# sch_AGV_MCU.net
KiCad netlist of a schematic drawn in Altium Designer
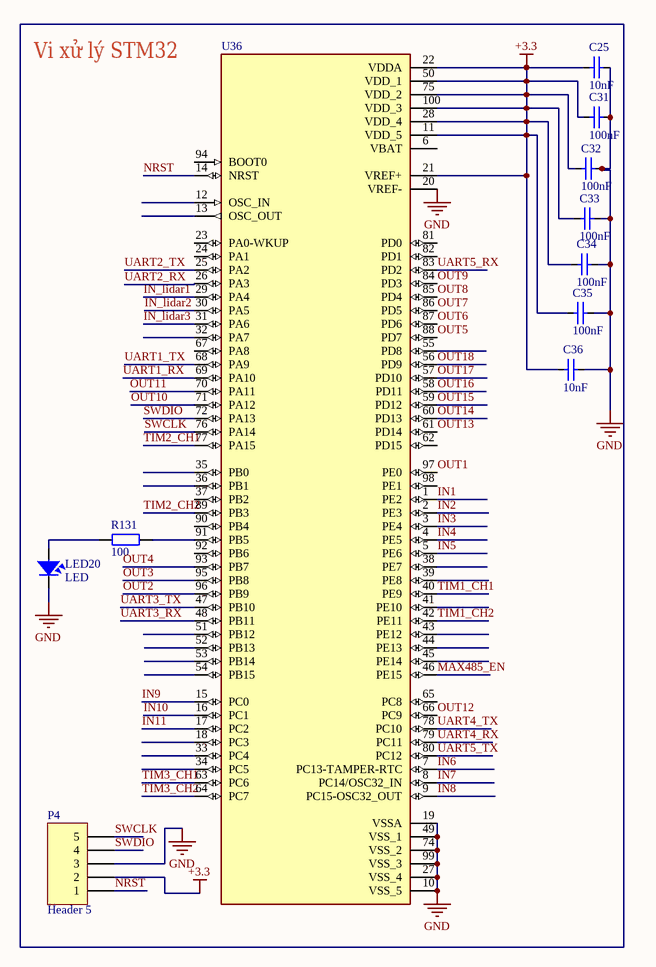
[diagram p0: sch_AGV_MCU.SchDoc]

(export (version "E")
  (design (tool "Eeschema 10.0.6"))
  (components
    (comp (ref "C25")
      (value "10nF")
      (footprint "CAP_0805")
      (description "Capacitor")
      (fields (field (name "PUBLISHER") "Altium Limited"))
      (libsource (lib "schelib_AGVcontrol") (part "CapSMD"))
    )
    (comp (ref "C31")
      (value "100nF")
      (footprint "CAP_0805")
      (description "Capacitor")
      (fields (field (name "PUBLISHER") "Altium Limited"))
      (libsource (lib "schelib_AGVcontrol") (part "CapSMD"))
    )
    (comp (ref "C32")
      (value "100nF")
      (footprint "CAP_0805")
      (description "Capacitor")
      (fields (field (name "PUBLISHER") "Altium Limited"))
      (libsource (lib "schelib_AGVcontrol") (part "CapSMD"))
    )
    (comp (ref "C33")
      (value "100nF")
      (footprint "CAP_0805")
      (description "Capacitor")
      (fields (field (name "PUBLISHER") "Altium Limited"))
      (libsource (lib "schelib_AGVcontrol") (part "CapSMD"))
    )
    (comp (ref "C34")
      (value "100nF")
      (footprint "CAP_0805")
      (description "Capacitor")
      (fields (field (name "PUBLISHER") "Altium Limited"))
      (libsource (lib "schelib_AGVcontrol") (part "CapSMD"))
    )
    (comp (ref "C35")
      (value "100nF")
      (footprint "CAP_0805")
      (description "Capacitor")
      (fields (field (name "PUBLISHER") "Altium Limited"))
      (libsource (lib "schelib_AGVcontrol") (part "CapSMD"))
    )
    (comp (ref "C36")
      (value "10nF")
      (footprint "CAP_0805")
      (description "Capacitor")
      (fields (field (name "PUBLISHER") "Altium Limited"))
      (libsource (lib "schelib_AGVcontrol") (part "CapSMD"))
    )
    (comp (ref "LED20")
      (value "LED")
      (footprint "LED_BLUE_SMD_0805")
      (description "LED Single colour Green and Red")
      (libsource (lib "schelib_AGVcontrol") (part "LED"))
    )
    (comp (ref "P4")
      (value "Header 5")
      (footprint "HDR5")
      (description "Header, 5-Pin")
      (fields (field (name "PUBLISHER") "Altium Limited"))
      (libsource (lib "schelib_AGVcontrol") (part "Header 5"))
    )
    (comp (ref "R131")
      (value "100")
      (footprint "RES_SMD_0805")
      (description "Resistor")
      (fields
        (field (name "MANUFACTURER") "Generic Components")
        (field (name "PUBLISHER") "Altium Hobart Technology Centre")
      )
      (libsource (lib "schelib_AGVcontrol") (part "Res"))
    )
    (comp (ref "U36")
      (value "~")
      (footprint "QFP50P1600X1600X160-100N")
      (description "ARMÂ® CortexÂ®-M3 STM32F1 Microcontroller IC 32-Bit 72MHz 512KB (512K x 8) FLASH 100-LQFP (14x14)")
      (fields (field (name "MF") "STMicroelectronics") (field (name "MP") "STM32F103VET6"))
      (libsource (lib "schelib_AGVcontrol") (part "STM32F103VET6"))
    )
  )
  (nets
    (net (code "1") (name "+3.3") (class "Default")
      (node (ref "C25") (pin "1") (pinfunction "1_1") (pintype "passive"))
      (node (ref "C31") (pin "1") (pinfunction "1_1") (pintype "passive"))
      (node (ref "C32") (pin "1") (pinfunction "1_1") (pintype "passive"))
      (node (ref "C33") (pin "1") (pinfunction "1_1") (pintype "passive"))
      (node (ref "C34") (pin "1") (pinfunction "1_1") (pintype "passive"))
      (node (ref "C35") (pin "1") (pinfunction "1_1") (pintype "passive"))
      (node (ref "C36") (pin "1") (pinfunction "1_1") (pintype "passive"))
      (node (ref "P4") (pin "2") (pinfunction "2_2") (pintype "passive"))
      (node (ref "U36") (pin "100") (pinfunction "VDD_3_100") (pintype "power_in"))
      (node (ref "U36") (pin "11") (pinfunction "VDD_5_11") (pintype "power_in"))
      (node (ref "U36") (pin "21") (pinfunction "VREF+_21") (pintype "power_in"))
      (node (ref "U36") (pin "22") (pinfunction "VDDA_22") (pintype "power_in"))
      (node (ref "U36") (pin "28") (pinfunction "VDD_4_28") (pintype "power_in"))
      (node (ref "U36") (pin "50") (pinfunction "VDD_1_50") (pintype "power_in"))
      (node (ref "U36") (pin "75") (pinfunction "VDD_2_75") (pintype "power_in"))
    )
    (net (code "2") (name "/IN1") (class "Default")
      (node (ref "U36") (pin "1") (pinfunction "PE2_1") (pintype "bidirectional"))
    )
    (net (code "3") (name "/IN2") (class "Default")
      (node (ref "U36") (pin "2") (pinfunction "PE3_2") (pintype "bidirectional"))
    )
    (net (code "4") (name "/IN3") (class "Default")
      (node (ref "U36") (pin "3") (pinfunction "PE4_3") (pintype "bidirectional"))
    )
    (net (code "5") (name "/IN4") (class "Default")
      (node (ref "U36") (pin "4") (pinfunction "PE5_4") (pintype "bidirectional"))
    )
    (net (code "6") (name "/IN5") (class "Default")
      (node (ref "U36") (pin "5") (pinfunction "PE6_5") (pintype "bidirectional"))
    )
    (net (code "7") (name "/IN6") (class "Default")
      (node (ref "U36") (pin "7") (pinfunction "PC13-TAMPER-RTC_7") (pintype "bidirectional"))
    )
    (net (code "8") (name "/IN7") (class "Default")
      (node (ref "U36") (pin "8") (pinfunction "PC14/OSC32_IN_8") (pintype "bidirectional"))
    )
    (net (code "9") (name "/IN8") (class "Default")
      (node (ref "U36") (pin "9") (pinfunction "PC15-OSC32_OUT_9") (pintype "bidirectional"))
    )
    (net (code "10") (name "/IN9") (class "Default")
      (node (ref "U36") (pin "15") (pinfunction "PC0_15") (pintype "bidirectional"))
    )
    (net (code "11") (name "/IN10") (class "Default")
      (node (ref "U36") (pin "16") (pinfunction "PC1_16") (pintype "bidirectional"))
    )
    (net (code "12") (name "/IN11") (class "Default")
      (node (ref "U36") (pin "17") (pinfunction "PC2_17") (pintype "bidirectional"))
    )
    (net (code "13") (name "/IN_lidar1") (class "Default")
      (node (ref "U36") (pin "29") (pinfunction "PA4_29") (pintype "bidirectional"))
    )
    (net (code "14") (name "/IN_lidar2") (class "Default")
      (node (ref "U36") (pin "30") (pinfunction "PA5_30") (pintype "bidirectional"))
    )
    (net (code "15") (name "/IN_lidar3") (class "Default")
      (node (ref "U36") (pin "31") (pinfunction "PA6_31") (pintype "bidirectional"))
    )
    (net (code "16") (name "/MAX485_EN") (class "Default")
      (node (ref "U36") (pin "46") (pinfunction "PE15_46") (pintype "bidirectional"))
    )
    (net (code "17") (name "/NRST") (class "Default")
      (node (ref "P4") (pin "1") (pinfunction "1_1") (pintype "passive"))
      (node (ref "U36") (pin "14") (pinfunction "NRST_14") (pintype "bidirectional"))
    )
    (net (code "18") (name "/OUT1") (class "Default")
      (node (ref "U36") (pin "97") (pinfunction "PE0_97") (pintype "bidirectional"))
    )
    (net (code "19") (name "/OUT2") (class "Default")
      (node (ref "U36") (pin "96") (pinfunction "PB9_96") (pintype "bidirectional"))
    )
    (net (code "20") (name "/OUT3") (class "Default")
      (node (ref "U36") (pin "95") (pinfunction "PB8_95") (pintype "bidirectional"))
    )
    (net (code "21") (name "/OUT4") (class "Default")
      (node (ref "U36") (pin "93") (pinfunction "PB7_93") (pintype "bidirectional"))
    )
    (net (code "22") (name "/OUT5") (class "Default")
      (node (ref "U36") (pin "88") (pinfunction "PD7_88") (pintype "bidirectional"))
    )
    (net (code "23") (name "/OUT6") (class "Default")
      (node (ref "U36") (pin "87") (pinfunction "PD6_87") (pintype "bidirectional"))
    )
    (net (code "24") (name "/OUT7") (class "Default")
      (node (ref "U36") (pin "86") (pinfunction "PD5_86") (pintype "bidirectional"))
    )
    (net (code "25") (name "/OUT8") (class "Default")
      (node (ref "U36") (pin "85") (pinfunction "PD4_85") (pintype "bidirectional"))
    )
    (net (code "26") (name "/OUT9") (class "Default")
      (node (ref "U36") (pin "84") (pinfunction "PD3_84") (pintype "bidirectional"))
    )
    (net (code "27") (name "/OUT10") (class "Default")
      (node (ref "U36") (pin "71") (pinfunction "PA12_71") (pintype "bidirectional"))
    )
    (net (code "28") (name "/OUT11") (class "Default")
      (node (ref "U36") (pin "70") (pinfunction "PA11_70") (pintype "bidirectional"))
    )
    (net (code "29") (name "/OUT12") (class "Default")
      (node (ref "U36") (pin "66") (pinfunction "PC9_66") (pintype "bidirectional"))
    )
    (net (code "30") (name "/OUT13") (class "Default")
      (node (ref "U36") (pin "61") (pinfunction "PD14_61") (pintype "bidirectional"))
    )
    (net (code "31") (name "/OUT14") (class "Default")
      (node (ref "U36") (pin "60") (pinfunction "PD13_60") (pintype "bidirectional"))
    )
    (net (code "32") (name "/OUT15") (class "Default")
      (node (ref "U36") (pin "59") (pinfunction "PD12_59") (pintype "bidirectional"))
    )
    (net (code "33") (name "/OUT16") (class "Default")
      (node (ref "U36") (pin "58") (pinfunction "PD11_58") (pintype "bidirectional"))
    )
    (net (code "34") (name "/OUT17") (class "Default")
      (node (ref "U36") (pin "57") (pinfunction "PD10_57") (pintype "bidirectional"))
    )
    (net (code "35") (name "/OUT18") (class "Default")
      (node (ref "U36") (pin "56") (pinfunction "PD9_56") (pintype "bidirectional"))
    )
    (net (code "36") (name "/SWCLK") (class "Default")
      (node (ref "P4") (pin "5") (pinfunction "5_5") (pintype "passive"))
      (node (ref "U36") (pin "76") (pinfunction "PA14_76") (pintype "bidirectional"))
    )
    (net (code "37") (name "/SWDIO") (class "Default")
      (node (ref "P4") (pin "4") (pinfunction "4_4") (pintype "passive"))
      (node (ref "U36") (pin "72") (pinfunction "PA13_72") (pintype "bidirectional"))
    )
    (net (code "38") (name "/TIM1_CH1") (class "Default")
      (node (ref "U36") (pin "40") (pinfunction "PE9_40") (pintype "bidirectional"))
    )
    (net (code "39") (name "/TIM1_CH2") (class "Default")
      (node (ref "U36") (pin "42") (pinfunction "PE11_42") (pintype "bidirectional"))
    )
    (net (code "40") (name "/TIM2_CH1") (class "Default")
      (node (ref "U36") (pin "77") (pinfunction "PA15_77") (pintype "bidirectional"))
    )
    (net (code "41") (name "/TIM2_CH2") (class "Default")
      (node (ref "U36") (pin "89") (pinfunction "PB3_89") (pintype "bidirectional"))
    )
    (net (code "42") (name "/TIM3_CH1") (class "Default")
      (node (ref "U36") (pin "63") (pinfunction "PC6_63") (pintype "bidirectional"))
    )
    (net (code "43") (name "/TIM3_CH2") (class "Default")
      (node (ref "U36") (pin "64") (pinfunction "PC7_64") (pintype "bidirectional"))
    )
    (net (code "44") (name "/UART1_RX") (class "Default")
      (node (ref "U36") (pin "69") (pinfunction "PA10_69") (pintype "bidirectional"))
    )
    (net (code "45") (name "/UART1_TX") (class "Default")
      (node (ref "U36") (pin "68") (pinfunction "PA9_68") (pintype "bidirectional"))
    )
    (net (code "46") (name "/UART2_RX") (class "Default")
      (node (ref "U36") (pin "26") (pinfunction "PA3_26") (pintype "bidirectional"))
    )
    (net (code "47") (name "/UART2_TX") (class "Default")
      (node (ref "U36") (pin "25") (pinfunction "PA2_25") (pintype "bidirectional"))
    )
    (net (code "48") (name "/UART3_RX") (class "Default")
      (node (ref "U36") (pin "48") (pinfunction "PB11_48") (pintype "bidirectional"))
    )
    (net (code "49") (name "/UART3_TX") (class "Default")
      (node (ref "U36") (pin "47") (pinfunction "PB10_47") (pintype "bidirectional"))
    )
    (net (code "50") (name "/UART4_RX") (class "Default")
      (node (ref "U36") (pin "79") (pinfunction "PC11_79") (pintype "bidirectional"))
    )
    (net (code "51") (name "/UART4_TX") (class "Default")
      (node (ref "U36") (pin "78") (pinfunction "PC10_78") (pintype "bidirectional"))
    )
    (net (code "52") (name "/UART5_RX") (class "Default")
      (node (ref "U36") (pin "83") (pinfunction "PD2_83") (pintype "bidirectional"))
    )
    (net (code "53") (name "/UART5_TX") (class "Default")
      (node (ref "U36") (pin "80") (pinfunction "PC12_80") (pintype "bidirectional"))
    )
    (net (code "54") (name "GND") (class "Default")
      (node (ref "C25") (pin "2") (pinfunction "2_2") (pintype "passive"))
      (node (ref "C31") (pin "2") (pinfunction "2_2") (pintype "passive"))
      (node (ref "C32") (pin "2") (pinfunction "2_2") (pintype "passive"))
      (node (ref "C33") (pin "2") (pinfunction "2_2") (pintype "passive"))
      (node (ref "C34") (pin "2") (pinfunction "2_2") (pintype "passive"))
      (node (ref "C35") (pin "2") (pinfunction "2_2") (pintype "passive"))
      (node (ref "C36") (pin "2") (pinfunction "2_2") (pintype "passive"))
      (node (ref "LED20") (pin "2") (pinfunction "2_2") (pintype "passive"))
      (node (ref "P4") (pin "3") (pinfunction "3_3") (pintype "passive"))
      (node (ref "U36") (pin "10") (pinfunction "VSS_5_10") (pintype "power_in"))
      (node (ref "U36") (pin "19") (pinfunction "VSSA_19") (pintype "power_in"))
      (node (ref "U36") (pin "20") (pinfunction "VREF-_20") (pintype "power_in"))
      (node (ref "U36") (pin "27") (pinfunction "VSS_4_27") (pintype "power_in"))
      (node (ref "U36") (pin "49") (pinfunction "VSS_1_49") (pintype "power_in"))
      (node (ref "U36") (pin "74") (pinfunction "VSS_2_74") (pintype "power_in"))
      (node (ref "U36") (pin "99") (pinfunction "VSS_3_99") (pintype "power_in"))
    )
    (net (code "55") (name "Net-(LED20-Pad1)") (class "Default")
      (node (ref "LED20") (pin "1") (pinfunction "1_1") (pintype "passive"))
      (node (ref "R131") (pin "1") (pinfunction "1_1") (pintype "passive"))
    )
    (net (code "56") (name "Net-(U36-PB5)") (class "Default")
      (node (ref "R131") (pin "2") (pinfunction "2_2") (pintype "passive"))
      (node (ref "U36") (pin "91") (pinfunction "PB5_91") (pintype "bidirectional"))
    )
    (net (code "57") (name "unconnected-(U36-BOOT0-Pad94)") (class "Default")
      (node (ref "U36") (pin "94") (pinfunction "BOOT0_94") (pintype "input"))
    )
    (net (code "58") (name "unconnected-(U36-OSC_IN-Pad12)") (class "Default")
      (node (ref "U36") (pin "12") (pinfunction "OSC_IN_12") (pintype "input"))
    )
    (net (code "59") (name "unconnected-(U36-OSC_OUT-Pad13)") (class "Default")
      (node (ref "U36") (pin "13") (pinfunction "OSC_OUT_13") (pintype "output"))
    )
    (net (code "60") (name "unconnected-(U36-PA0-WKUP-Pad23)") (class "Default")
      (node (ref "U36") (pin "23") (pinfunction "PA0-WKUP_23") (pintype "bidirectional"))
    )
    (net (code "61") (name "unconnected-(U36-PA1-Pad24)") (class "Default")
      (node (ref "U36") (pin "24") (pinfunction "PA1_24") (pintype "bidirectional"))
    )
    (net (code "62") (name "unconnected-(U36-PA7-Pad32)") (class "Default")
      (node (ref "U36") (pin "32") (pinfunction "PA7_32") (pintype "bidirectional"))
    )
    (net (code "63") (name "unconnected-(U36-PA8-Pad67)") (class "Default")
      (node (ref "U36") (pin "67") (pinfunction "PA8_67") (pintype "bidirectional"))
    )
    (net (code "64") (name "unconnected-(U36-PB0-Pad35)") (class "Default")
      (node (ref "U36") (pin "35") (pinfunction "PB0_35") (pintype "bidirectional"))
    )
    (net (code "65") (name "unconnected-(U36-PB1-Pad36)") (class "Default")
      (node (ref "U36") (pin "36") (pinfunction "PB1_36") (pintype "bidirectional"))
    )
    (net (code "66") (name "unconnected-(U36-PB2-Pad37)") (class "Default")
      (node (ref "U36") (pin "37") (pinfunction "PB2_37") (pintype "bidirectional"))
    )
    (net (code "67") (name "unconnected-(U36-PB4-Pad90)") (class "Default")
      (node (ref "U36") (pin "90") (pinfunction "PB4_90") (pintype "bidirectional"))
    )
    (net (code "68") (name "unconnected-(U36-PB6-Pad92)") (class "Default")
      (node (ref "U36") (pin "92") (pinfunction "PB6_92") (pintype "bidirectional"))
    )
    (net (code "69") (name "unconnected-(U36-PB12-Pad51)") (class "Default")
      (node (ref "U36") (pin "51") (pinfunction "PB12_51") (pintype "bidirectional"))
    )
    (net (code "70") (name "unconnected-(U36-PB13-Pad52)") (class "Default")
      (node (ref "U36") (pin "52") (pinfunction "PB13_52") (pintype "bidirectional"))
    )
    (net (code "71") (name "unconnected-(U36-PB14-Pad53)") (class "Default")
      (node (ref "U36") (pin "53") (pinfunction "PB14_53") (pintype "bidirectional"))
    )
    (net (code "72") (name "unconnected-(U36-PB15-Pad54)") (class "Default")
      (node (ref "U36") (pin "54") (pinfunction "PB15_54") (pintype "bidirectional"))
    )
    (net (code "73") (name "unconnected-(U36-PC3-Pad18)") (class "Default")
      (node (ref "U36") (pin "18") (pinfunction "PC3_18") (pintype "bidirectional"))
    )
    (net (code "74") (name "unconnected-(U36-PC4-Pad33)") (class "Default")
      (node (ref "U36") (pin "33") (pinfunction "PC4_33") (pintype "bidirectional"))
    )
    (net (code "75") (name "unconnected-(U36-PC5-Pad34)") (class "Default")
      (node (ref "U36") (pin "34") (pinfunction "PC5_34") (pintype "bidirectional"))
    )
    (net (code "76") (name "unconnected-(U36-PC8-Pad65)") (class "Default")
      (node (ref "U36") (pin "65") (pinfunction "PC8_65") (pintype "bidirectional"))
    )
    (net (code "77") (name "unconnected-(U36-PD0-Pad81)") (class "Default")
      (node (ref "U36") (pin "81") (pinfunction "PD0_81") (pintype "bidirectional"))
    )
    (net (code "78") (name "unconnected-(U36-PD1-Pad82)") (class "Default")
      (node (ref "U36") (pin "82") (pinfunction "PD1_82") (pintype "bidirectional"))
    )
    (net (code "79") (name "unconnected-(U36-PD8-Pad55)") (class "Default")
      (node (ref "U36") (pin "55") (pinfunction "PD8_55") (pintype "bidirectional"))
    )
    (net (code "80") (name "unconnected-(U36-PD15-Pad62)") (class "Default")
      (node (ref "U36") (pin "62") (pinfunction "PD15_62") (pintype "bidirectional"))
    )
    (net (code "81") (name "unconnected-(U36-PE1-Pad98)") (class "Default")
      (node (ref "U36") (pin "98") (pinfunction "PE1_98") (pintype "bidirectional"))
    )
    (net (code "82") (name "unconnected-(U36-PE7-Pad38)") (class "Default")
      (node (ref "U36") (pin "38") (pinfunction "PE7_38") (pintype "bidirectional"))
    )
    (net (code "83") (name "unconnected-(U36-PE8-Pad39)") (class "Default")
      (node (ref "U36") (pin "39") (pinfunction "PE8_39") (pintype "bidirectional"))
    )
    (net (code "84") (name "unconnected-(U36-PE10-Pad41)") (class "Default")
      (node (ref "U36") (pin "41") (pinfunction "PE10_41") (pintype "bidirectional"))
    )
    (net (code "85") (name "unconnected-(U36-PE12-Pad43)") (class "Default")
      (node (ref "U36") (pin "43") (pinfunction "PE12_43") (pintype "bidirectional"))
    )
    (net (code "86") (name "unconnected-(U36-PE13-Pad44)") (class "Default")
      (node (ref "U36") (pin "44") (pinfunction "PE13_44") (pintype "bidirectional"))
    )
    (net (code "87") (name "unconnected-(U36-PE14-Pad45)") (class "Default")
      (node (ref "U36") (pin "45") (pinfunction "PE14_45") (pintype "bidirectional"))
    )
    (net (code "88") (name "unconnected-(U36-VBAT-Pad6)") (class "Default")
      (node (ref "U36") (pin "6") (pinfunction "VBAT_6") (pintype "power_in"))
    )
  )
)
